# Sheet.net
KiCad netlist of a schematic drawn in Altium Designer
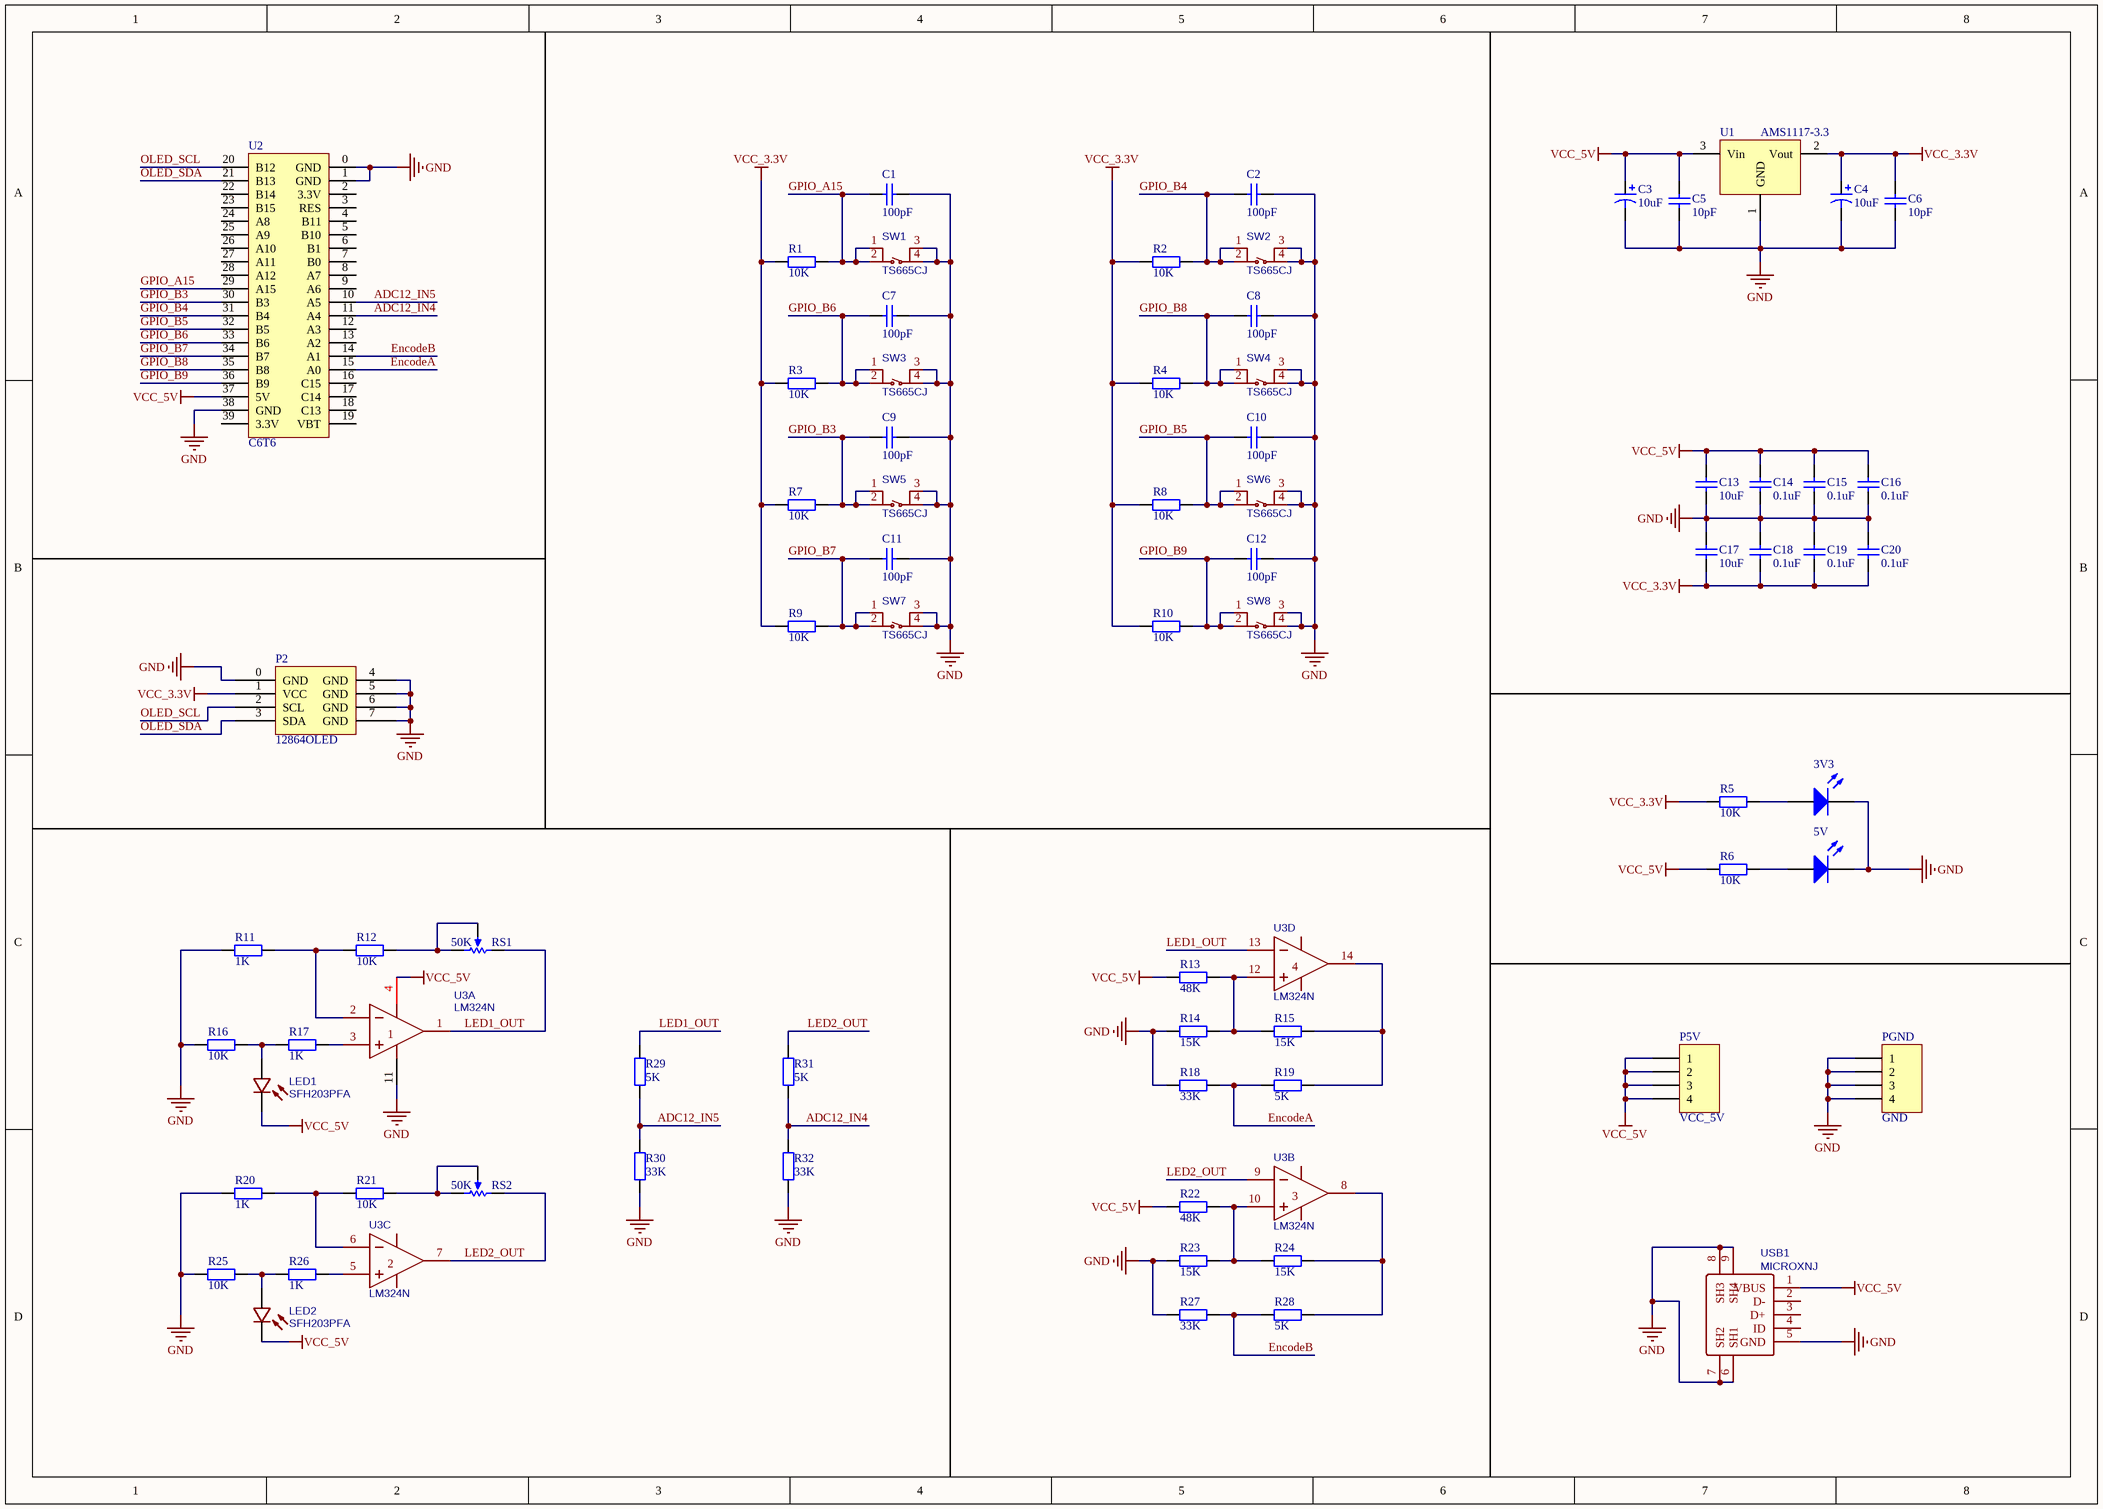
[diagram p0: Sheet.SchDoc]

(export (version "E")
  (design (tool "Eeschema 10.0.6"))
  (components
    (comp (ref "3V3")
      (value "~")
      (footprint "6-0805_M")
      (description "Typical BLUE SiC LED")
      (fields (field (name "PUBLISHER") "Altium Limited"))
      (libsource (lib "Miscellaneous Devices") (part "LED3"))
    )
    (comp (ref "5V")
      (value "~")
      (footprint "6-0805_M")
      (description "Typical BLUE SiC LED")
      (fields (field (name "PUBLISHER") "Altium Limited"))
      (libsource (lib "Miscellaneous Devices") (part "LED3"))
    )
    (comp (ref "C1")
      (value "100pF")
      (footprint "CAP-LISHI")
      (description "Capacitor (Semiconductor SIM Model)")
      (fields (field (name "Comment") "Cap Semi") (field (name "PUBLISHER") "Altium Limited"))
      (libsource (lib "Miscellaneous Devices") (part "Cap Semi"))
    )
    (comp (ref "C2")
      (value "100pF")
      (footprint "CAP-LISHI")
      (description "Capacitor (Semiconductor SIM Model)")
      (fields (field (name "Comment") "Cap Semi") (field (name "PUBLISHER") "Altium Limited"))
      (libsource (lib "Miscellaneous Devices") (part "Cap Semi"))
    )
    (comp (ref "C3")
      (value "10uF")
      (footprint "CAP-LISHI")
      (description "Polarized Capacitor (Surface Mount)")
      (fields (field (name "Comment") "Cap Pol3") (field (name "PUBLISHER") "Altium Limited"))
      (libsource (lib "Miscellaneous Devices") (part "Cap Pol3"))
    )
    (comp (ref "C4")
      (value "10uF")
      (footprint "CAP-LISHI")
      (description "Polarized Capacitor (Surface Mount)")
      (fields (field (name "Comment") "Cap Pol3") (field (name "PUBLISHER") "Altium Limited"))
      (libsource (lib "Miscellaneous Devices") (part "Cap Pol3"))
    )
    (comp (ref "C5")
      (value "10pF")
      (footprint "CAP-LISHI")
      (description "Capacitor (Semiconductor SIM Model)")
      (fields (field (name "Comment") "Cap Semi") (field (name "PUBLISHER") "Altium Limited"))
      (libsource (lib "Miscellaneous Devices") (part "Cap Semi"))
    )
    (comp (ref "C6")
      (value "10pF")
      (footprint "CAP-LISHI")
      (description "Capacitor (Semiconductor SIM Model)")
      (fields (field (name "Comment") "Cap Semi") (field (name "PUBLISHER") "Altium Limited"))
      (libsource (lib "Miscellaneous Devices") (part "Cap Semi"))
    )
    (comp (ref "C7")
      (value "100pF")
      (footprint "CAP-LISHI")
      (description "Capacitor (Semiconductor SIM Model)")
      (fields (field (name "Comment") "Cap Semi") (field (name "PUBLISHER") "Altium Limited"))
      (libsource (lib "Miscellaneous Devices") (part "Cap Semi"))
    )
    (comp (ref "C8")
      (value "100pF")
      (footprint "CAP-LISHI")
      (description "Capacitor (Semiconductor SIM Model)")
      (fields (field (name "Comment") "Cap Semi") (field (name "PUBLISHER") "Altium Limited"))
      (libsource (lib "Miscellaneous Devices") (part "Cap Semi"))
    )
    (comp (ref "C9")
      (value "100pF")
      (footprint "CAP-LISHI")
      (description "Capacitor (Semiconductor SIM Model)")
      (fields (field (name "Comment") "Cap Semi") (field (name "PUBLISHER") "Altium Limited"))
      (libsource (lib "Miscellaneous Devices") (part "Cap Semi"))
    )
    (comp (ref "C10")
      (value "100pF")
      (footprint "CAP-LISHI")
      (description "Capacitor (Semiconductor SIM Model)")
      (fields (field (name "Comment") "Cap Semi") (field (name "PUBLISHER") "Altium Limited"))
      (libsource (lib "Miscellaneous Devices") (part "Cap Semi"))
    )
    (comp (ref "C11")
      (value "100pF")
      (footprint "CAP-LISHI")
      (description "Capacitor (Semiconductor SIM Model)")
      (fields (field (name "Comment") "Cap Semi") (field (name "PUBLISHER") "Altium Limited"))
      (libsource (lib "Miscellaneous Devices") (part "Cap Semi"))
    )
    (comp (ref "C12")
      (value "100pF")
      (footprint "CAP-LISHI")
      (description "Capacitor (Semiconductor SIM Model)")
      (fields (field (name "Comment") "Cap Semi") (field (name "PUBLISHER") "Altium Limited"))
      (libsource (lib "Miscellaneous Devices") (part "Cap Semi"))
    )
    (comp (ref "C13")
      (value "10uF")
      (footprint "CAP-LISHI")
      (description "Capacitor (Semiconductor SIM Model)")
      (fields (field (name "Comment") "Cap Semi") (field (name "PUBLISHER") "Altium Limited"))
      (libsource (lib "Miscellaneous Devices") (part "Cap Semi"))
    )
    (comp (ref "C14")
      (value "0.1uF")
      (footprint "CAP-LISHI")
      (description "Capacitor (Semiconductor SIM Model)")
      (fields (field (name "Comment") "Cap Semi") (field (name "PUBLISHER") "Altium Limited"))
      (libsource (lib "Miscellaneous Devices") (part "Cap Semi"))
    )
    (comp (ref "C15")
      (value "0.1uF")
      (footprint "CAP-LISHI")
      (description "Capacitor (Semiconductor SIM Model)")
      (fields (field (name "Comment") "Cap Semi") (field (name "PUBLISHER") "Altium Limited"))
      (libsource (lib "Miscellaneous Devices") (part "Cap Semi"))
    )
    (comp (ref "C16")
      (value "0.1uF")
      (footprint "CAP-LISHI")
      (description "Capacitor (Semiconductor SIM Model)")
      (fields (field (name "Comment") "Cap Semi") (field (name "PUBLISHER") "Altium Limited"))
      (libsource (lib "Miscellaneous Devices") (part "Cap Semi"))
    )
    (comp (ref "C17")
      (value "10uF")
      (footprint "CAP-LISHI")
      (description "Capacitor (Semiconductor SIM Model)")
      (fields (field (name "Comment") "Cap Semi") (field (name "PUBLISHER") "Altium Limited"))
      (libsource (lib "Miscellaneous Devices") (part "Cap Semi"))
    )
    (comp (ref "C18")
      (value "0.1uF")
      (footprint "CAP-LISHI")
      (description "Capacitor (Semiconductor SIM Model)")
      (fields (field (name "Comment") "Cap Semi") (field (name "PUBLISHER") "Altium Limited"))
      (libsource (lib "Miscellaneous Devices") (part "Cap Semi"))
    )
    (comp (ref "C19")
      (value "0.1uF")
      (footprint "CAP-LISHI")
      (description "Capacitor (Semiconductor SIM Model)")
      (fields (field (name "Comment") "Cap Semi") (field (name "PUBLISHER") "Altium Limited"))
      (libsource (lib "Miscellaneous Devices") (part "Cap Semi"))
    )
    (comp (ref "C20")
      (value "0.1uF")
      (footprint "CAP-LISHI")
      (description "Capacitor (Semiconductor SIM Model)")
      (fields (field (name "Comment") "Cap Semi") (field (name "PUBLISHER") "Altium Limited"))
      (libsource (lib "Miscellaneous Devices") (part "Cap Semi"))
    )
    (comp (ref "LED1")
      (value "SFH203PFA")
      (footprint "LED-TH_BD5.9-P2.54-FD")
      (fields (field (name "BOM_SUPPLIER PART") "C554984") (field (name "CONTRIBUTOR") "LCSC"))
      (libsource (lib "Schlib") (part "SFH203PFA"))
    )
    (comp (ref "LED2")
      (value "SFH203PFA")
      (footprint "LED-TH_BD5.9-P2.54-FD")
      (fields (field (name "BOM_SUPPLIER PART") "C554984") (field (name "CONTRIBUTOR") "LCSC"))
      (libsource (lib "Schlib") (part "SFH203PFA"))
    )
    (comp (ref "P2")
      (value "12864OLED")
      (footprint "12864_0.96_OLED")
      (libsource (lib "Schlib") (part "12864OLED"))
    )
    (comp (ref "P5V")
      (value "VCC_5V")
      (footprint "HDR1X4")
      (description "Header, 4-Pin")
      (fields (field (name "PUBLISHER") "Altium Limited"))
      (libsource (lib "Miscellaneous Connectors") (part "Header 4"))
    )
    (comp (ref "PGND")
      (value "GND")
      (footprint "HDR1X4")
      (description "Header, 4-Pin")
      (fields (field (name "PUBLISHER") "Altium Limited"))
      (libsource (lib "Miscellaneous Connectors") (part "Header 4"))
    )
    (comp (ref "R1")
      (value "10K")
      (footprint "AXIAL-0.4")
      (description "Resistor")
      (fields (field (name "Comment") "Res2") (field (name "PUBLISHER") "Altium Limited"))
      (libsource (lib "Miscellaneous Devices") (part "Res2"))
    )
    (comp (ref "R2")
      (value "10K")
      (footprint "AXIAL-0.4")
      (description "Resistor")
      (fields (field (name "Comment") "Res2") (field (name "PUBLISHER") "Altium Limited"))
      (libsource (lib "Miscellaneous Devices") (part "Res2"))
    )
    (comp (ref "R3")
      (value "10K")
      (footprint "AXIAL-0.4")
      (description "Resistor")
      (fields (field (name "Comment") "Res2") (field (name "PUBLISHER") "Altium Limited"))
      (libsource (lib "Miscellaneous Devices") (part "Res2"))
    )
    (comp (ref "R4")
      (value "10K")
      (footprint "AXIAL-0.4")
      (description "Resistor")
      (fields (field (name "Comment") "Res2") (field (name "PUBLISHER") "Altium Limited"))
      (libsource (lib "Miscellaneous Devices") (part "Res2"))
    )
    (comp (ref "R5")
      (value "10K")
      (footprint "AXIAL-0.4")
      (description "Resistor")
      (fields (field (name "Comment") "Res2") (field (name "PUBLISHER") "Altium Limited"))
      (libsource (lib "Miscellaneous Devices") (part "Res2"))
    )
    (comp (ref "R6")
      (value "10K")
      (footprint "AXIAL-0.4")
      (description "Resistor")
      (fields (field (name "Comment") "Res2") (field (name "PUBLISHER") "Altium Limited"))
      (libsource (lib "Miscellaneous Devices") (part "Res2"))
    )
    (comp (ref "R7")
      (value "10K")
      (footprint "AXIAL-0.4")
      (description "Resistor")
      (fields (field (name "Comment") "Res2") (field (name "PUBLISHER") "Altium Limited"))
      (libsource (lib "Miscellaneous Devices") (part "Res2"))
    )
    (comp (ref "R8")
      (value "10K")
      (footprint "AXIAL-0.4")
      (description "Resistor")
      (fields (field (name "Comment") "Res2") (field (name "PUBLISHER") "Altium Limited"))
      (libsource (lib "Miscellaneous Devices") (part "Res2"))
    )
    (comp (ref "R9")
      (value "10K")
      (footprint "AXIAL-0.4")
      (description "Resistor")
      (fields (field (name "Comment") "Res2") (field (name "PUBLISHER") "Altium Limited"))
      (libsource (lib "Miscellaneous Devices") (part "Res2"))
    )
    (comp (ref "R10")
      (value "10K")
      (footprint "AXIAL-0.4")
      (description "Resistor")
      (fields (field (name "Comment") "Res2") (field (name "PUBLISHER") "Altium Limited"))
      (libsource (lib "Miscellaneous Devices") (part "Res2"))
    )
    (comp (ref "R11")
      (value "1K")
      (footprint "AXIAL-0.4")
      (description "Resistor")
      (fields (field (name "Comment") "Res2") (field (name "PUBLISHER") "Altium Limited"))
      (libsource (lib "Miscellaneous Devices") (part "Res2"))
    )
    (comp (ref "R12")
      (value "10K")
      (footprint "AXIAL-0.4")
      (description "Resistor")
      (fields (field (name "Comment") "Res2") (field (name "PUBLISHER") "Altium Limited"))
      (libsource (lib "Miscellaneous Devices") (part "Res2"))
    )
    (comp (ref "R13")
      (value "48K")
      (footprint "AXIAL-0.4")
      (description "Resistor")
      (fields (field (name "Comment") "Res2") (field (name "PUBLISHER") "Altium Limited"))
      (libsource (lib "") (part "Res2_2"))
    )
    (comp (ref "R14")
      (value "15K")
      (footprint "AXIAL-0.4")
      (description "Resistor")
      (fields (field (name "Comment") "Res2") (field (name "PUBLISHER") "Altium Limited"))
      (libsource (lib "") (part "Res2_2"))
    )
    (comp (ref "R15")
      (value "15K")
      (footprint "AXIAL-0.4")
      (description "Resistor")
      (fields (field (name "Comment") "Res2") (field (name "PUBLISHER") "Altium Limited"))
      (libsource (lib "") (part "Res2_2"))
    )
    (comp (ref "R16")
      (value "10K")
      (footprint "AXIAL-0.4")
      (description "Resistor")
      (fields (field (name "Comment") "Res2") (field (name "PUBLISHER") "Altium Limited"))
      (libsource (lib "Miscellaneous Devices") (part "Res2"))
    )
    (comp (ref "R17")
      (value "1K")
      (footprint "AXIAL-0.4")
      (description "Resistor")
      (fields (field (name "Comment") "Res2") (field (name "PUBLISHER") "Altium Limited"))
      (libsource (lib "Miscellaneous Devices") (part "Res2"))
    )
    (comp (ref "R18")
      (value "33K")
      (footprint "AXIAL-0.4")
      (description "Resistor")
      (fields (field (name "Comment") "Res2") (field (name "PUBLISHER") "Altium Limited"))
      (libsource (lib "Miscellaneous Devices") (part "Res2"))
    )
    (comp (ref "R19")
      (value "5K")
      (footprint "AXIAL-0.4")
      (description "Resistor")
      (fields (field (name "Comment") "Res2") (field (name "PUBLISHER") "Altium Limited"))
      (libsource (lib "Miscellaneous Devices") (part "Res2"))
    )
    (comp (ref "R20")
      (value "1K")
      (footprint "AXIAL-0.4")
      (description "Resistor")
      (fields (field (name "Comment") "Res2") (field (name "PUBLISHER") "Altium Limited"))
      (libsource (lib "Miscellaneous Devices") (part "Res2"))
    )
    (comp (ref "R21")
      (value "10K")
      (footprint "AXIAL-0.4")
      (description "Resistor")
      (fields (field (name "Comment") "Res2") (field (name "PUBLISHER") "Altium Limited"))
      (libsource (lib "Miscellaneous Devices") (part "Res2"))
    )
    (comp (ref "R22")
      (value "48K")
      (footprint "AXIAL-0.4")
      (description "Resistor")
      (fields (field (name "Comment") "Res2") (field (name "PUBLISHER") "Altium Limited"))
      (libsource (lib "") (part "Res2_2"))
    )
    (comp (ref "R23")
      (value "15K")
      (footprint "AXIAL-0.4")
      (description "Resistor")
      (fields (field (name "Comment") "Res2") (field (name "PUBLISHER") "Altium Limited"))
      (libsource (lib "") (part "Res2_2"))
    )
    (comp (ref "R24")
      (value "15K")
      (footprint "AXIAL-0.4")
      (description "Resistor")
      (fields (field (name "Comment") "Res2") (field (name "PUBLISHER") "Altium Limited"))
      (libsource (lib "") (part "Res2_2"))
    )
    (comp (ref "R25")
      (value "10K")
      (footprint "AXIAL-0.4")
      (description "Resistor")
      (fields (field (name "Comment") "Res2") (field (name "PUBLISHER") "Altium Limited"))
      (libsource (lib "Miscellaneous Devices") (part "Res2"))
    )
    (comp (ref "R26")
      (value "1K")
      (footprint "AXIAL-0.4")
      (description "Resistor")
      (fields (field (name "Comment") "Res2") (field (name "PUBLISHER") "Altium Limited"))
      (libsource (lib "Miscellaneous Devices") (part "Res2"))
    )
    (comp (ref "R27")
      (value "33K")
      (footprint "AXIAL-0.4")
      (description "Resistor")
      (fields (field (name "Comment") "Res2") (field (name "PUBLISHER") "Altium Limited"))
      (libsource (lib "Miscellaneous Devices") (part "Res2"))
    )
    (comp (ref "R28")
      (value "5K")
      (footprint "AXIAL-0.4")
      (description "Resistor")
      (fields (field (name "Comment") "Res2") (field (name "PUBLISHER") "Altium Limited"))
      (libsource (lib "Miscellaneous Devices") (part "Res2"))
    )
    (comp (ref "R29")
      (value "5K")
      (footprint "AXIAL-0.4")
      (description "Resistor")
      (fields (field (name "Comment") "Res2") (field (name "PUBLISHER") "Altium Limited"))
      (libsource (lib "") (part "Res2_1"))
    )
    (comp (ref "R30")
      (value "33K")
      (footprint "AXIAL-0.4")
      (description "Resistor")
      (fields (field (name "Comment") "Res2") (field (name "PUBLISHER") "Altium Limited"))
      (libsource (lib "") (part "Res2_1"))
    )
    (comp (ref "R31")
      (value "5K")
      (footprint "AXIAL-0.4")
      (description "Resistor")
      (fields (field (name "Comment") "Res2") (field (name "PUBLISHER") "Altium Limited"))
      (libsource (lib "") (part "Res2_1"))
    )
    (comp (ref "R32")
      (value "33K")
      (footprint "AXIAL-0.4")
      (description "Resistor")
      (fields (field (name "Comment") "Res2") (field (name "PUBLISHER") "Altium Limited"))
      (libsource (lib "") (part "Res2_1"))
    )
    (comp (ref "RS1")
      (value "50K")
      (footprint "RES-ADJ-TH_3P-L10.0-W10.0-P2.50-L")
      (description "Potentiometer")
      (fields (field (name "Comment") "RPot") (field (name "PUBLISHER") "Altium Limited"))
      (libsource (lib "Miscellaneous Devices") (part "RPot"))
    )
    (comp (ref "RS2")
      (value "50K")
      (footprint "RES-ADJ-TH_3P-L10.0-W10.0-P2.50-L")
      (description "Potentiometer")
      (fields (field (name "Comment") "RPot") (field (name "PUBLISHER") "Altium Limited"))
      (libsource (lib "Miscellaneous Devices") (part "RPot"))
    )
    (comp (ref "SW1")
      (value "TS665CJ")
      (footprint "SW-TH_4P-L6.0-W6.0-P4.50-LS6.5")
      (fields (field (name "BOM_SUPPLIER PART") "C393938") (field (name "CONTRIBUTOR") "LCSC"))
      (libsource (lib "Schlib") (part "TS665CJ"))
    )
    (comp (ref "SW2")
      (value "TS665CJ")
      (footprint "SW-TH_4P-L6.0-W6.0-P4.50-LS6.5")
      (fields (field (name "BOM_SUPPLIER PART") "C393938") (field (name "CONTRIBUTOR") "LCSC"))
      (libsource (lib "Schlib") (part "TS665CJ"))
    )
    (comp (ref "SW3")
      (value "TS665CJ")
      (footprint "SW-TH_4P-L6.0-W6.0-P4.50-LS6.5")
      (fields (field (name "BOM_SUPPLIER PART") "C393938") (field (name "CONTRIBUTOR") "LCSC"))
      (libsource (lib "Schlib") (part "TS665CJ"))
    )
    (comp (ref "SW4")
      (value "TS665CJ")
      (footprint "SW-TH_4P-L6.0-W6.0-P4.50-LS6.5")
      (fields (field (name "BOM_SUPPLIER PART") "C393938") (field (name "CONTRIBUTOR") "LCSC"))
      (libsource (lib "Schlib") (part "TS665CJ"))
    )
    (comp (ref "SW5")
      (value "TS665CJ")
      (footprint "SW-TH_4P-L6.0-W6.0-P4.50-LS6.5")
      (fields (field (name "BOM_SUPPLIER PART") "C393938") (field (name "CONTRIBUTOR") "LCSC"))
      (libsource (lib "Schlib") (part "TS665CJ"))
    )
    (comp (ref "SW6")
      (value "TS665CJ")
      (footprint "SW-TH_4P-L6.0-W6.0-P4.50-LS6.5")
      (fields (field (name "BOM_SUPPLIER PART") "C393938") (field (name "CONTRIBUTOR") "LCSC"))
      (libsource (lib "Schlib") (part "TS665CJ"))
    )
    (comp (ref "SW7")
      (value "TS665CJ")
      (footprint "SW-TH_4P-L6.0-W6.0-P4.50-LS6.5")
      (fields (field (name "BOM_SUPPLIER PART") "C393938") (field (name "CONTRIBUTOR") "LCSC"))
      (libsource (lib "Schlib") (part "TS665CJ"))
    )
    (comp (ref "SW8")
      (value "TS665CJ")
      (footprint "SW-TH_4P-L6.0-W6.0-P4.50-LS6.5")
      (fields (field (name "BOM_SUPPLIER PART") "C393938") (field (name "CONTRIBUTOR") "LCSC"))
      (libsource (lib "Schlib") (part "TS665CJ"))
    )
    (comp (ref "U1")
      (value "AMS1117-3.3")
      (footprint "SOT-89-3_L4.5-W2.5-P1.50-LS4.2-BR")
      (libsource (lib "Schlib") (part "AMS1117-3.3_C880752"))
    )
    (comp (ref "U2")
      (value "C6T6")
      (footprint "STM32F103C6T6")
      (libsource (lib "Schlib") (part "STM32F103C6T6"))
    )
    (comp (ref "U3")
      (value "LM324N")
      (footprint "DIP-14_L19.4-W6.4-P2.54-LS7.6-BL")
      (fields (field (name "BOM_SUPPLIER PART") "C725320") (field (name "SUBPART_NO") "1"))
      (libsource (lib "Schlib") (part "LM324N"))
    )
    (comp (ref "USB1")
      (value "MICROXNJ")
      (footprint "MICRO-USB-SMD_MICROXNJ")
      (fields
        (field (name "BOM_SUPPLIER PART") "C404969")
        (field (name "BOM_MANUFACTURER PART") "MicroXNJ")
        (field (name "CONTRIBUTOR") "LCSC")
      )
      (libsource (lib "Schlib") (part "MICROXNJ"))
    )
  )
  (nets
    (net (code "1") (name "/ADC12_IN4") (class "Default")
      (node (ref "R31") (pin "1") (pinfunction "1_1") (pintype "passive"))
      (node (ref "R32") (pin "2") (pinfunction "2_2") (pintype "passive"))
      (node (ref "U2") (pin "11") (pinfunction "A4_11") (pintype "passive"))
    )
    (net (code "2") (name "/ADC12_IN5") (class "Default")
      (node (ref "R29") (pin "1") (pinfunction "1_1") (pintype "passive"))
      (node (ref "R30") (pin "2") (pinfunction "2_2") (pintype "passive"))
      (node (ref "U2") (pin "10") (pinfunction "A5_10") (pintype "passive"))
    )
    (net (code "3") (name "/EncodeA") (class "Default")
      (node (ref "R18") (pin "2") (pinfunction "2_2") (pintype "passive"))
      (node (ref "R19") (pin "1") (pinfunction "1_1") (pintype "passive"))
      (node (ref "U2") (pin "15") (pinfunction "A0_15") (pintype "passive"))
    )
    (net (code "4") (name "/EncodeB") (class "Default")
      (node (ref "R27") (pin "2") (pinfunction "2_2") (pintype "passive"))
      (node (ref "R28") (pin "1") (pinfunction "1_1") (pintype "passive"))
      (node (ref "U2") (pin "14") (pinfunction "A1_14") (pintype "passive"))
    )
    (net (code "5") (name "/GPIO_A15") (class "Default")
      (node (ref "C1") (pin "1") (pinfunction "1_1") (pintype "passive"))
      (node (ref "R1") (pin "2") (pinfunction "2_2") (pintype "passive"))
      (node (ref "SW1") (pin "1") (pinfunction "A_1") (pintype "passive"))
      (node (ref "SW1") (pin "2") (pinfunction "B_2") (pintype "passive"))
      (node (ref "U2") (pin "29") (pinfunction "A15_29") (pintype "passive"))
    )
    (net (code "6") (name "/GPIO_B3") (class "Default")
      (node (ref "C9") (pin "1") (pinfunction "1_1") (pintype "passive"))
      (node (ref "R7") (pin "2") (pinfunction "2_2") (pintype "passive"))
      (node (ref "SW5") (pin "1") (pinfunction "A_1") (pintype "passive"))
      (node (ref "SW5") (pin "2") (pinfunction "B_2") (pintype "passive"))
      (node (ref "U2") (pin "30") (pinfunction "B3_30") (pintype "passive"))
    )
    (net (code "7") (name "/GPIO_B4") (class "Default")
      (node (ref "C2") (pin "1") (pinfunction "1_1") (pintype "passive"))
      (node (ref "R2") (pin "2") (pinfunction "2_2") (pintype "passive"))
      (node (ref "SW2") (pin "1") (pinfunction "A_1") (pintype "passive"))
      (node (ref "SW2") (pin "2") (pinfunction "B_2") (pintype "passive"))
      (node (ref "U2") (pin "31") (pinfunction "B4_31") (pintype "passive"))
    )
    (net (code "8") (name "/GPIO_B5") (class "Default")
      (node (ref "C10") (pin "1") (pinfunction "1_1") (pintype "passive"))
      (node (ref "R8") (pin "2") (pinfunction "2_2") (pintype "passive"))
      (node (ref "SW6") (pin "1") (pinfunction "A_1") (pintype "passive"))
      (node (ref "SW6") (pin "2") (pinfunction "B_2") (pintype "passive"))
      (node (ref "U2") (pin "32") (pinfunction "B5_32") (pintype "passive"))
    )
    (net (code "9") (name "/GPIO_B6") (class "Default")
      (node (ref "C7") (pin "1") (pinfunction "1_1") (pintype "passive"))
      (node (ref "R3") (pin "2") (pinfunction "2_2") (pintype "passive"))
      (node (ref "SW3") (pin "1") (pinfunction "A_1") (pintype "passive"))
      (node (ref "SW3") (pin "2") (pinfunction "B_2") (pintype "passive"))
      (node (ref "U2") (pin "33") (pinfunction "B6_33") (pintype "passive"))
    )
    (net (code "10") (name "/GPIO_B7") (class "Default")
      (node (ref "C11") (pin "1") (pinfunction "1_1") (pintype "passive"))
      (node (ref "R9") (pin "2") (pinfunction "2_2") (pintype "passive"))
      (node (ref "SW7") (pin "1") (pinfunction "A_1") (pintype "passive"))
      (node (ref "SW7") (pin "2") (pinfunction "B_2") (pintype "passive"))
      (node (ref "U2") (pin "34") (pinfunction "B7_34") (pintype "passive"))
    )
    (net (code "11") (name "/GPIO_B8") (class "Default")
      (node (ref "C8") (pin "1") (pinfunction "1_1") (pintype "passive"))
      (node (ref "R4") (pin "2") (pinfunction "2_2") (pintype "passive"))
      (node (ref "SW4") (pin "1") (pinfunction "A_1") (pintype "passive"))
      (node (ref "SW4") (pin "2") (pinfunction "B_2") (pintype "passive"))
      (node (ref "U2") (pin "35") (pinfunction "B8_35") (pintype "passive"))
    )
    (net (code "12") (name "/GPIO_B9") (class "Default")
      (node (ref "C12") (pin "1") (pinfunction "1_1") (pintype "passive"))
      (node (ref "R10") (pin "2") (pinfunction "2_2") (pintype "passive"))
      (node (ref "SW8") (pin "1") (pinfunction "A_1") (pintype "passive"))
      (node (ref "SW8") (pin "2") (pinfunction "B_2") (pintype "passive"))
      (node (ref "U2") (pin "36") (pinfunction "B9_36") (pintype "passive"))
    )
    (net (code "13") (name "/LED1_OUT") (class "Default")
      (node (ref "R29") (pin "2") (pinfunction "2_2") (pintype "passive"))
      (node (ref "RS1") (pin "1") (pinfunction "TOP_1") (pintype "passive"))
      (node (ref "U3") (pin "1") (pinfunction "OUT1_1") (pintype "passive"))
      (node (ref "U3") (pin "13") (pinfunction "IN4-_13") (pintype "passive"))
    )
    (net (code "14") (name "/LED2_OUT") (class "Default")
      (node (ref "R31") (pin "2") (pinfunction "2_2") (pintype "passive"))
      (node (ref "RS2") (pin "1") (pinfunction "TOP_1") (pintype "passive"))
      (node (ref "U3") (pin "7") (pinfunction "OUT2_7") (pintype "passive"))
      (node (ref "U3") (pin "9") (pinfunction "IN3-_9") (pintype "passive"))
    )
    (net (code "15") (name "/OLED_SCL") (class "Default")
      (node (ref "P2") (pin "2") (pinfunction "SCL_2") (pintype "passive"))
      (node (ref "U2") (pin "20") (pinfunction "B12_20") (pintype "passive"))
    )
    (net (code "16") (name "/OLED_SDA") (class "Default")
      (node (ref "P2") (pin "3") (pinfunction "SDA_3") (pintype "passive"))
      (node (ref "U2") (pin "21") (pinfunction "B13_21") (pintype "passive"))
    )
    (net (code "17") (name "GND") (class "Default")
      (node (ref "3V3") (pin "2") (pinfunction "K_2") (pintype "passive"))
      (node (ref "5V") (pin "2") (pinfunction "K_2") (pintype "passive"))
      (node (ref "C1") (pin "2") (pinfunction "2_2") (pintype "passive"))
      (node (ref "C10") (pin "2") (pinfunction "2_2") (pintype "passive"))
      (node (ref "C11") (pin "2") (pinfunction "2_2") (pintype "passive"))
      (node (ref "C12") (pin "2") (pinfunction "2_2") (pintype "passive"))
      (node (ref "C13") (pin "1") (pinfunction "1_1") (pintype "passive"))
      (node (ref "C14") (pin "1") (pinfunction "1_1") (pintype "passive"))
      (node (ref "C15") (pin "1") (pinfunction "1_1") (pintype "passive"))
      (node (ref "C16") (pin "1") (pinfunction "1_1") (pintype "passive"))
      (node (ref "C17") (pin "1") (pinfunction "1_1") (pintype "passive"))
      (node (ref "C18") (pin "1") (pinfunction "1_1") (pintype "passive"))
      (node (ref "C19") (pin "1") (pinfunction "1_1") (pintype "passive"))
      (node (ref "C2") (pin "2") (pinfunction "2_2") (pintype "passive"))
      (node (ref "C20") (pin "1") (pinfunction "1_1") (pintype "passive"))
      (node (ref "C3") (pin "2") (pinfunction "2_2") (pintype "passive"))
      (node (ref "C4") (pin "2") (pinfunction "2_2") (pintype "passive"))
      (node (ref "C5") (pin "1") (pinfunction "1_1") (pintype "passive"))
      (node (ref "C6") (pin "1") (pinfunction "1_1") (pintype "passive"))
      (node (ref "C7") (pin "2") (pinfunction "2_2") (pintype "passive"))
      (node (ref "C8") (pin "2") (pinfunction "2_2") (pintype "passive"))
      (node (ref "C9") (pin "2") (pinfunction "2_2") (pintype "passive"))
      (node (ref "P2") (pin "0") (pinfunction "GND_0") (pintype "passive"))
      (node (ref "P2") (pin "4") (pinfunction "GND_4") (pintype "passive"))
      (node (ref "P2") (pin "5") (pinfunction "GND_5") (pintype "passive"))
      (node (ref "P2") (pin "6") (pinfunction "GND_6") (pintype "passive"))
      (node (ref "P2") (pin "7") (pinfunction "GND_7") (pintype "passive"))
      (node (ref "PGND") (pin "1") (pinfunction "1_1") (pintype "passive"))
      (node (ref "PGND") (pin "2") (pinfunction "2_2") (pintype "passive"))
      (node (ref "PGND") (pin "3") (pinfunction "3_3") (pintype "passive"))
      (node (ref "PGND") (pin "4") (pinfunction "4_4") (pintype "passive"))
      (node (ref "R11") (pin "1") (pinfunction "1_1") (pintype "passive"))
      (node (ref "R14") (pin "2") (pinfunction "2_2") (pintype "passive"))
      (node (ref "R16") (pin "1") (pinfunction "1_1") (pintype "passive"))
      (node (ref "R18") (pin "1") (pinfunction "1_1") (pintype "passive"))
      (node (ref "R20") (pin "1") (pinfunction "1_1") (pintype "passive"))
      (node (ref "R23") (pin "2") (pinfunction "2_2") (pintype "passive"))
      (node (ref "R25") (pin "1") (pinfunction "1_1") (pintype "passive"))
      (node (ref "R27") (pin "1") (pinfunction "1_1") (pintype "passive"))
      (node (ref "R30") (pin "1") (pinfunction "1_1") (pintype "passive"))
      (node (ref "R32") (pin "1") (pinfunction "1_1") (pintype "passive"))
      (node (ref "SW1") (pin "3") (pinfunction "C_3") (pintype "passive"))
      (node (ref "SW1") (pin "4") (pinfunction "D_4") (pintype "passive"))
      (node (ref "SW2") (pin "3") (pinfunction "C_3") (pintype "passive"))
      (node (ref "SW2") (pin "4") (pinfunction "D_4") (pintype "passive"))
      (node (ref "SW3") (pin "3") (pinfunction "C_3") (pintype "passive"))
      (node (ref "SW3") (pin "4") (pinfunction "D_4") (pintype "passive"))
      (node (ref "SW4") (pin "3") (pinfunction "C_3") (pintype "passive"))
      (node (ref "SW4") (pin "4") (pinfunction "D_4") (pintype "passive"))
      (node (ref "SW5") (pin "3") (pinfunction "C_3") (pintype "passive"))
      (node (ref "SW5") (pin "4") (pinfunction "D_4") (pintype "passive"))
      (node (ref "SW6") (pin "3") (pinfunction "C_3") (pintype "passive"))
      (node (ref "SW6") (pin "4") (pinfunction "D_4") (pintype "passive"))
      (node (ref "SW7") (pin "3") (pinfunction "C_3") (pintype "passive"))
      (node (ref "SW7") (pin "4") (pinfunction "D_4") (pintype "passive"))
      (node (ref "SW8") (pin "3") (pinfunction "C_3") (pintype "passive"))
      (node (ref "SW8") (pin "4") (pinfunction "D_4") (pintype "passive"))
      (node (ref "U1") (pin "1") (pinfunction "GND_1") (pintype "passive"))
      (node (ref "U2") (pin "0") (pinfunction "GND_0") (pintype "passive"))
      (node (ref "U2") (pin "1") (pinfunction "GND_1") (pintype "passive"))
      (node (ref "U2") (pin "38") (pinfunction "GND_38") (pintype "passive"))
      (node (ref "U3") (pin "11") (pinfunction "GND_11") (pintype "passive"))
      (node (ref "USB1") (pin "5") (pinfunction "GND_5") (pintype "passive"))
      (node (ref "USB1") (pin "6") (pinfunction "SH1_6") (pintype "passive"))
      (node (ref "USB1") (pin "7") (pinfunction "SH2_7") (pintype "passive"))
      (node (ref "USB1") (pin "8") (pinfunction "SH3_8") (pintype "passive"))
      (node (ref "USB1") (pin "9") (pinfunction "SH4_9") (pintype "passive"))
    )
    (net (code "18") (name "Net-(3V3-A)") (class "Default")
      (node (ref "3V3") (pin "1") (pinfunction "A_1") (pintype "passive"))
      (node (ref "R5") (pin "2") (pinfunction "2_2") (pintype "passive"))
    )
    (net (code "19") (name "Net-(5V-A)") (class "Default")
      (node (ref "5V") (pin "1") (pinfunction "A_1") (pintype "passive"))
      (node (ref "R6") (pin "2") (pinfunction "2_2") (pintype "passive"))
    )
    (net (code "20") (name "Net-(LED1-C)") (class "Default")
      (node (ref "LED1") (pin "1") (pinfunction "C_1") (pintype "passive"))
      (node (ref "R16") (pin "2") (pinfunction "2_2") (pintype "passive"))
      (node (ref "R17") (pin "1") (pinfunction "1_1") (pintype "passive"))
    )
    (net (code "21") (name "Net-(LED2-C)") (class "Default")
      (node (ref "LED2") (pin "1") (pinfunction "C_1") (pintype "passive"))
      (node (ref "R25") (pin "2") (pinfunction "2_2") (pintype "passive"))
      (node (ref "R26") (pin "1") (pinfunction "1_1") (pintype "passive"))
    )
    (net (code "22") (name "Net-(RS1-BOT)") (class "Default")
      (node (ref "R12") (pin "2") (pinfunction "2_2") (pintype "passive"))
      (node (ref "RS1") (pin "2") (pinfunction "BOT_2") (pintype "passive"))
      (node (ref "RS1") (pin "3") (pinfunction "TAP_3") (pintype "passive"))
    )
    (net (code "23") (name "Net-(RS2-BOT)") (class "Default")
      (node (ref "R21") (pin "2") (pinfunction "2_2") (pintype "passive"))
      (node (ref "RS2") (pin "2") (pinfunction "BOT_2") (pintype "passive"))
      (node (ref "RS2") (pin "3") (pinfunction "TAP_3") (pintype "passive"))
    )
    (net (code "24") (name "Net-(U3A-IN1+)") (class "Default")
      (node (ref "R17") (pin "2") (pinfunction "2_2") (pintype "passive"))
      (node (ref "U3") (pin "3") (pinfunction "IN1+_3") (pintype "passive"))
    )
    (net (code "25") (name "Net-(U3A-IN1-)") (class "Default")
      (node (ref "R11") (pin "2") (pinfunction "2_2") (pintype "passive"))
      (node (ref "R12") (pin "1") (pinfunction "1_1") (pintype "passive"))
      (node (ref "U3") (pin "2") (pinfunction "IN1-_2") (pintype "passive"))
    )
    (net (code "26") (name "Net-(U3B-IN3+)") (class "Default")
      (node (ref "R22") (pin "1") (pinfunction "1_1") (pintype "passive"))
      (node (ref "R23") (pin "1") (pinfunction "1_1") (pintype "passive"))
      (node (ref "R24") (pin "2") (pinfunction "2_2") (pintype "passive"))
      (node (ref "U3") (pin "10") (pinfunction "IN3+_10") (pintype "passive"))
    )
    (net (code "27") (name "Net-(U3B-OUT3)") (class "Default")
      (node (ref "R24") (pin "1") (pinfunction "1_1") (pintype "passive"))
      (node (ref "R28") (pin "2") (pinfunction "2_2") (pintype "passive"))
      (node (ref "U3") (pin "8") (pinfunction "OUT3_8") (pintype "passive"))
    )
    (net (code "28") (name "Net-(U3C-IN2+)") (class "Default")
      (node (ref "R26") (pin "2") (pinfunction "2_2") (pintype "passive"))
      (node (ref "U3") (pin "5") (pinfunction "IN2+_5") (pintype "passive"))
    )
    (net (code "29") (name "Net-(U3C-IN2-)") (class "Default")
      (node (ref "R20") (pin "2") (pinfunction "2_2") (pintype "passive"))
      (node (ref "R21") (pin "1") (pinfunction "1_1") (pintype "passive"))
      (node (ref "U3") (pin "6") (pinfunction "IN2-_6") (pintype "passive"))
    )
    (net (code "30") (name "Net-(U3D-IN4+)") (class "Default")
      (node (ref "R13") (pin "1") (pinfunction "1_1") (pintype "passive"))
      (node (ref "R14") (pin "1") (pinfunction "1_1") (pintype "passive"))
      (node (ref "R15") (pin "2") (pinfunction "2_2") (pintype "passive"))
      (node (ref "U3") (pin "12") (pinfunction "IN4+_12") (pintype "passive"))
    )
    (net (code "31") (name "Net-(U3D-OUT4)") (class "Default")
      (node (ref "R15") (pin "1") (pinfunction "1_1") (pintype "passive"))
      (node (ref "R19") (pin "2") (pinfunction "2_2") (pintype "passive"))
      (node (ref "U3") (pin "14") (pinfunction "OUT4_14") (pintype "passive"))
    )
    (net (code "32") (name "VCC_3.3V") (class "Default")
      (node (ref "C17") (pin "2") (pinfunction "2_2") (pintype "passive"))
      (node (ref "C18") (pin "2") (pinfunction "2_2") (pintype "passive"))
      (node (ref "C19") (pin "2") (pinfunction "2_2") (pintype "passive"))
      (node (ref "C20") (pin "2") (pinfunction "2_2") (pintype "passive"))
      (node (ref "C4") (pin "1") (pinfunction "1_1") (pintype "passive"))
      (node (ref "C6") (pin "2") (pinfunction "2_2") (pintype "passive"))
      (node (ref "P2") (pin "1") (pinfunction "VCC_1") (pintype "passive"))
      (node (ref "R1") (pin "1") (pinfunction "1_1") (pintype "passive"))
      (node (ref "R10") (pin "1") (pinfunction "1_1") (pintype "passive"))
      (node (ref "R2") (pin "1") (pinfunction "1_1") (pintype "passive"))
      (node (ref "R3") (pin "1") (pinfunction "1_1") (pintype "passive"))
      (node (ref "R4") (pin "1") (pinfunction "1_1") (pintype "passive"))
      (node (ref "R5") (pin "1") (pinfunction "1_1") (pintype "passive"))
      (node (ref "R7") (pin "1") (pinfunction "1_1") (pintype "passive"))
      (node (ref "R8") (pin "1") (pinfunction "1_1") (pintype "passive"))
      (node (ref "R9") (pin "1") (pinfunction "1_1") (pintype "passive"))
      (node (ref "U1") (pin "2") (pinfunction "Vout_2") (pintype "passive"))
    )
    (net (code "33") (name "VCC_5V") (class "Default")
      (node (ref "C13") (pin "2") (pinfunction "2_2") (pintype "passive"))
      (node (ref "C14") (pin "2") (pinfunction "2_2") (pintype "passive"))
      (node (ref "C15") (pin "2") (pinfunction "2_2") (pintype "passive"))
      (node (ref "C16") (pin "2") (pinfunction "2_2") (pintype "passive"))
      (node (ref "C3") (pin "1") (pinfunction "1_1") (pintype "passive"))
      (node (ref "C5") (pin "2") (pinfunction "2_2") (pintype "passive"))
      (node (ref "LED1") (pin "2") (pinfunction "E_2") (pintype "passive"))
      (node (ref "LED2") (pin "2") (pinfunction "E_2") (pintype "passive"))
      (node (ref "P5V") (pin "1") (pinfunction "1_1") (pintype "passive"))
      (node (ref "P5V") (pin "2") (pinfunction "2_2") (pintype "passive"))
      (node (ref "P5V") (pin "3") (pinfunction "3_3") (pintype "passive"))
      (node (ref "P5V") (pin "4") (pinfunction "4_4") (pintype "passive"))
      (node (ref "R13") (pin "2") (pinfunction "2_2") (pintype "passive"))
      (node (ref "R22") (pin "2") (pinfunction "2_2") (pintype "passive"))
      (node (ref "R6") (pin "1") (pinfunction "1_1") (pintype "passive"))
      (node (ref "U1") (pin "3") (pinfunction "Vin_3") (pintype "passive"))
      (node (ref "U2") (pin "37") (pinfunction "5V_37") (pintype "passive"))
      (node (ref "U3") (pin "4") (pinfunction "VCC_4") (pintype "passive"))
      (node (ref "USB1") (pin "1") (pinfunction "VBUS_1") (pintype "passive"))
    )
    (net (code "34") (name "unconnected-(U2-3.3V-Pad2)") (class "Default")
      (node (ref "U2") (pin "2") (pinfunction "3.3V_2") (pintype "passive"))
    )
    (net (code "35") (name "unconnected-(U2-3.3V-Pad39)") (class "Default")
      (node (ref "U2") (pin "39") (pinfunction "3.3V_39") (pintype "passive"))
    )
    (net (code "36") (name "unconnected-(U2-A2-Pad13)") (class "Default")
      (node (ref "U2") (pin "13") (pinfunction "A2_13") (pintype "passive"))
    )
    (net (code "37") (name "unconnected-(U2-A3-Pad12)") (class "Default")
      (node (ref "U2") (pin "12") (pinfunction "A3_12") (pintype "passive"))
    )
    (net (code "38") (name "unconnected-(U2-A6-Pad9)") (class "Default")
      (node (ref "U2") (pin "9") (pinfunction "A6_9") (pintype "passive"))
    )
    (net (code "39") (name "unconnected-(U2-A7-Pad8)") (class "Default")
      (node (ref "U2") (pin "8") (pinfunction "A7_8") (pintype "passive"))
    )
    (net (code "40") (name "unconnected-(U2-A8-Pad24)") (class "Default")
      (node (ref "U2") (pin "24") (pinfunction "A8_24") (pintype "passive"))
    )
    (net (code "41") (name "unconnected-(U2-A9-Pad25)") (class "Default")
      (node (ref "U2") (pin "25") (pinfunction "A9_25") (pintype "passive"))
    )
    (net (code "42") (name "unconnected-(U2-A10-Pad26)") (class "Default")
      (node (ref "U2") (pin "26") (pinfunction "A10_26") (pintype "passive"))
    )
    (net (code "43") (name "unconnected-(U2-A11-Pad27)") (class "Default")
      (node (ref "U2") (pin "27") (pinfunction "A11_27") (pintype "passive"))
    )
    (net (code "44") (name "unconnected-(U2-A12-Pad28)") (class "Default")
      (node (ref "U2") (pin "28") (pinfunction "A12_28") (pintype "passive"))
    )
    (net (code "45") (name "unconnected-(U2-B0-Pad7)") (class "Default")
      (node (ref "U2") (pin "7") (pinfunction "B0_7") (pintype "passive"))
    )
    (net (code "46") (name "unconnected-(U2-B1-Pad6)") (class "Default")
      (node (ref "U2") (pin "6") (pinfunction "B1_6") (pintype "passive"))
    )
    (net (code "47") (name "unconnected-(U2-B10-Pad5)") (class "Default")
      (node (ref "U2") (pin "5") (pinfunction "B10_5") (pintype "passive"))
    )
    (net (code "48") (name "unconnected-(U2-B11-Pad4)") (class "Default")
      (node (ref "U2") (pin "4") (pinfunction "B11_4") (pintype "passive"))
    )
    (net (code "49") (name "unconnected-(U2-B14-Pad22)") (class "Default")
      (node (ref "U2") (pin "22") (pinfunction "B14_22") (pintype "passive"))
    )
    (net (code "50") (name "unconnected-(U2-B15-Pad23)") (class "Default")
      (node (ref "U2") (pin "23") (pinfunction "B15_23") (pintype "passive"))
    )
    (net (code "51") (name "unconnected-(U2-C13-Pad18)") (class "Default")
      (node (ref "U2") (pin "18") (pinfunction "C13_18") (pintype "passive"))
    )
    (net (code "52") (name "unconnected-(U2-C14-Pad17)") (class "Default")
      (node (ref "U2") (pin "17") (pinfunction "C14_17") (pintype "passive"))
    )
    (net (code "53") (name "unconnected-(U2-C15-Pad16)") (class "Default")
      (node (ref "U2") (pin "16") (pinfunction "C15_16") (pintype "passive"))
    )
    (net (code "54") (name "unconnected-(U2-RES-Pad3)") (class "Default")
      (node (ref "U2") (pin "3") (pinfunction "RES_3") (pintype "passive"))
    )
    (net (code "55") (name "unconnected-(U2-VBT-Pad19)") (class "Default")
      (node (ref "U2") (pin "19") (pinfunction "VBT_19") (pintype "passive"))
    )
    (net (code "56") (name "unconnected-(USB1-D+-Pad3)") (class "Default")
      (node (ref "USB1") (pin "3") (pinfunction "D+_3") (pintype "passive"))
    )
    (net (code "57") (name "unconnected-(USB1-D--Pad2)") (class "Default")
      (node (ref "USB1") (pin "2") (pinfunction "D-_2") (pintype "passive"))
    )
    (net (code "58") (name "unconnected-(USB1-ID-Pad4)") (class "Default")
      (node (ref "USB1") (pin "4") (pinfunction "ID_4") (pintype "passive"))
    )
  )
)
